# MCU.net
KiCad netlist of a schematic drawn in Altium Designer
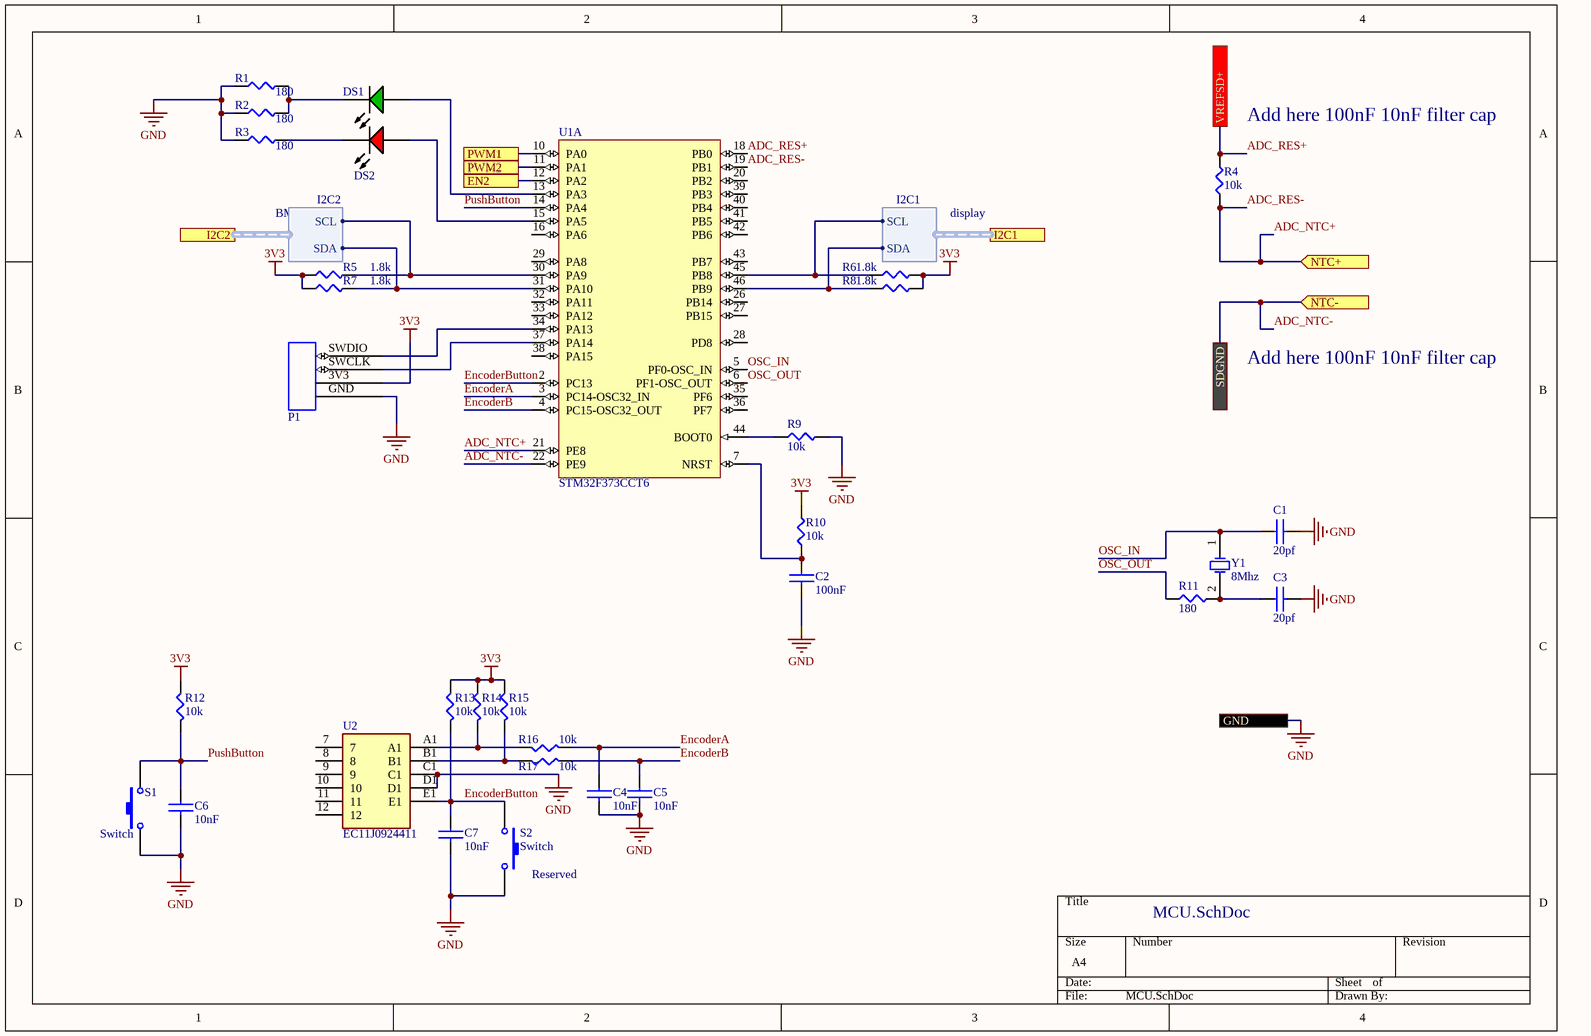
[diagram p0: MCU.SchDoc]

(export (version "E")
  (design (tool "Eeschema 10.0.6"))
  (components
    (comp (ref "C1")
      (value "20pf")
      (footprint "CAPC160X80X90L35N")
      (fields (field (name "LCSC PART #") "C1648") (field (name "PART NUMBER") "CL10C200JB8NNNC"))
      (libsource (lib "Miscellaneous") (part "capacitor"))
    )
    (comp (ref "C2")
      (value "100nF")
      (footprint "CAPC160X80X90L35N")
      (fields (field (name "LCSC PART #") "C14663") (field (name "PART NUMBER") "CC0603KRX7R9BB104"))
      (libsource (lib "Miscellaneous") (part "capacitor"))
    )
    (comp (ref "C3")
      (value "20pf")
      (footprint "CAPC160X80X90L35N")
      (fields (field (name "LCSC PART #") "C1648") (field (name "PART NUMBER") "CL10C200JB8NNNC"))
      (libsource (lib "Miscellaneous") (part "capacitor"))
    )
    (comp (ref "C4")
      (value "10nF")
      (footprint "CAPC160X80X90L35N")
      (fields (field (name "LCSC PART #") "C57112") (field (name "PART NUMBER") "0603B103K500NT"))
      (libsource (lib "Miscellaneous") (part "capacitor"))
    )
    (comp (ref "C5")
      (value "10nF")
      (footprint "CAPC160X80X90L35N")
      (fields (field (name "LCSC PART #") "C57112") (field (name "PART NUMBER") "0603B103K500NT"))
      (libsource (lib "Miscellaneous") (part "capacitor"))
    )
    (comp (ref "C6")
      (value "10nF")
      (footprint "CAPC160X80X90L35N")
      (fields (field (name "LCSC PART #") "C57112") (field (name "PART NUMBER") "0603B103K500NT"))
      (libsource (lib "Miscellaneous") (part "capacitor"))
    )
    (comp (ref "C7")
      (value "10nF")
      (footprint "CAPC160X80X90L35N")
      (fields (field (name "LCSC PART #") "C57112") (field (name "PART NUMBER") "0603B103K500NT"))
      (libsource (lib "Miscellaneous") (part "capacitor"))
    )
    (comp (ref "DS1")
      (value "19-217/GHC-YR1S2/3T")
      (footprint "LEDC160X80X60L30N")
      (description "Green LED")
      (fields (field (name "LCSC PART #") "C72043"))
      (libsource (lib "Miscellaneous") (part "LED"))
    )
    (comp (ref "DS2")
      (value "FC-2012HRK-620D")
      (footprint "LEDC200X125X110L30N")
      (description "Red LED")
      (fields (field (name "LCSC PART #") "C84256"))
      (libsource (lib "Miscellaneous") (part "RED LED"))
    )
    (comp (ref "P1") (value "SWD") (footprint "SWD") (libsource (lib "Miscellaneous") (part "SWD port")))
    (comp (ref "R1")
      (value "180")
      (footprint "RESC160X80X90L30N")
      (fields (field (name "PART NUMBER") "0603WAF1800T5E") (field (name "LCSC PART #") "C22828"))
      (libsource (lib "Miscellaneous") (part "Resistor"))
    )
    (comp (ref "R2")
      (value "180")
      (footprint "RESC160X80X90L30N")
      (fields (field (name "PART NUMBER") "0603WAF1800T5E") (field (name "LCSC PART #") "C22828"))
      (libsource (lib "Miscellaneous") (part "Resistor"))
    )
    (comp (ref "R3")
      (value "180")
      (footprint "RESC160X80X90L30N")
      (fields (field (name "PART NUMBER") "0603WAF1800T5E") (field (name "LCSC PART #") "C22828"))
      (libsource (lib "Miscellaneous") (part "Resistor"))
    )
    (comp (ref "R4")
      (value "10k")
      (footprint "RESC160X80X90L30N")
      (fields (field (name "PART NUMBER") "0603WAF1002T5E") (field (name "LCSC PART #") "C25804"))
      (libsource (lib "Miscellaneous") (part "Resistor"))
    )
    (comp (ref "R5")
      (value "1.8k")
      (footprint "RESC160X80X90L30N")
      (fields (field (name "PART NUMBER") "0603WAF1801T5E") (field (name "LCSC PART #") "C4177"))
      (libsource (lib "Miscellaneous") (part "Resistor"))
    )
    (comp (ref "R6")
      (value "1.8k")
      (footprint "RESC160X80X90L30N")
      (fields (field (name "PART NUMBER") "0603WAF1801T5E") (field (name "LCSC PART #") "C4177"))
      (libsource (lib "Miscellaneous") (part "Resistor"))
    )
    (comp (ref "R7")
      (value "1.8k")
      (footprint "RESC160X80X90L30N")
      (fields (field (name "PART NUMBER") "0603WAF1801T5E") (field (name "LCSC PART #") "C4177"))
      (libsource (lib "Miscellaneous") (part "Resistor"))
    )
    (comp (ref "R8")
      (value "1.8k")
      (footprint "RESC160X80X90L30N")
      (fields (field (name "PART NUMBER") "0603WAF1801T5E") (field (name "LCSC PART #") "C4177"))
      (libsource (lib "Miscellaneous") (part "Resistor"))
    )
    (comp (ref "R9")
      (value "10k")
      (footprint "RESC160X80X90L30N")
      (fields (field (name "PART NUMBER") "0603WAF1002T5E") (field (name "LCSC PART #") "C25804"))
      (libsource (lib "Miscellaneous") (part "Resistor"))
    )
    (comp (ref "R10")
      (value "10k")
      (footprint "RESC160X80X90L30N")
      (fields (field (name "PART NUMBER") "0603WAF1002T5E") (field (name "LCSC PART #") "C25804"))
      (libsource (lib "Miscellaneous") (part "Resistor"))
    )
    (comp (ref "R11")
      (value "180")
      (footprint "RESC160X80X90L30N")
      (fields (field (name "PART NUMBER") "0603WAF1800T5E") (field (name "LCSC PART #") "C22828"))
      (libsource (lib "Miscellaneous") (part "Resistor"))
    )
    (comp (ref "R12")
      (value "10k")
      (footprint "RESC160X80X90L30N")
      (fields (field (name "PART NUMBER") "0603WAF1002T5E") (field (name "LCSC PART #") "C25804"))
      (libsource (lib "Miscellaneous") (part "Resistor"))
    )
    (comp (ref "R13")
      (value "10k")
      (footprint "RESC160X80X90L30N")
      (fields (field (name "PART NUMBER") "0603WAF1002T5E") (field (name "LCSC PART #") "C25804"))
      (libsource (lib "Miscellaneous") (part "Resistor"))
    )
    (comp (ref "R14")
      (value "10k")
      (footprint "RESC160X80X90L30N")
      (fields (field (name "PART NUMBER") "0603WAF1002T5E") (field (name "LCSC PART #") "C25804"))
      (libsource (lib "Miscellaneous") (part "Resistor"))
    )
    (comp (ref "R15")
      (value "10k")
      (footprint "RESC160X80X90L30N")
      (fields (field (name "PART NUMBER") "0603WAF1002T5E") (field (name "LCSC PART #") "C25804"))
      (libsource (lib "Miscellaneous") (part "Resistor"))
    )
    (comp (ref "R16")
      (value "10k")
      (footprint "RESC160X80X90L30N")
      (fields (field (name "PART NUMBER") "0603WAF1002T5E") (field (name "LCSC PART #") "C25804"))
      (libsource (lib "Miscellaneous") (part "Resistor"))
    )
    (comp (ref "R17")
      (value "10k")
      (footprint "RESC160X80X90L30N")
      (fields (field (name "PART NUMBER") "0603WAF1002T5E") (field (name "LCSC PART #") "C25804"))
      (libsource (lib "Miscellaneous") (part "Resistor"))
    )
    (comp (ref "S1")
      (value "Switch")
      (footprint "Tactile switch")
      (fields (field (name "PART NUMBER") "TS-1187A-C-E-B") (field (name "PUBLISHER") "Altium Limited"))
      (libsource (lib "Miscellaneous") (part "Switch"))
    )
    (comp (ref "S2")
      (value "Switch")
      (footprint "Tactile switch")
      (fields (field (name "PART NUMBER") "TS-1187A-C-E-B") (field (name "PUBLISHER") "Altium Limited"))
      (libsource (lib "Miscellaneous") (part "Switch"))
    )
    (comp (ref "U1")
      (value "STM32F373CCT6")
      (footprint "STM-LQFP48_L")
      (fields (field (name "LCSC PART #") "C89403") (field (name "MANUFACTURER") "STMicroelectronics"))
      (libsource (lib "Miscellaneous") (part "STM32F373CCT6"))
    )
    (comp (ref "U2")
      (value "EC11J0924411")
      (footprint "EC11J0924411")
      (description "Rotary encoder")
      (fields (field (name "MOUSER2 PART NUMBER") "688-EC11J0924411"))
      (libsource (lib "Miscellaneous") (part "EC11J0924411"))
    )
    (comp (ref "Y1")
      (value "8Mhz")
      (footprint "5032")
      (description "Crystal Oscillator")
      (fields
        (field (name "PART NUMBER") "X50328MSB2GI")
        (field (name "LCSC PART #") "C115962")
        (field (name "PUBLISHER") "Altium Limited")
      )
      (libsource (lib "Miscellaneous") (part "XTAL"))
    )
  )
  (nets
    (net (code "3") (name "/ADC_NTC+") (class "Default")
      (node (ref "R4") (pin "1") (pinfunction "1_1") (pintype "passive"))
      (node (ref "U1") (pin "19") (pinfunction "PB1_19") (pintype "bidirectional"))
      (node (ref "U1") (pin "21") (pinfunction "PE8_21") (pintype "bidirectional"))
    )
    (net (code "4") (name "/ADC_NTC-") (class "Default")
      (node (ref "U1") (pin "22") (pinfunction "PE9_22") (pintype "bidirectional"))
    )
    (net (code "5") (name "/ADC_RES+") (class "Default")
      (node (ref "R4") (pin "2") (pinfunction "2_2") (pintype "passive"))
      (node (ref "U1") (pin "18") (pinfunction "PB0_18") (pintype "bidirectional"))
    )
    (net (code "6") (name "/EN2") (class "Default")
      (node (ref "U1") (pin "12") (pinfunction "PA2_12") (pintype "bidirectional"))
    )
    (net (code "7") (name "/EncoderA") (class "Default")
      (node (ref "C4") (pin "1") (pinfunction "1_1") (pintype "passive"))
      (node (ref "R16") (pin "2") (pinfunction "2_2") (pintype "passive"))
      (node (ref "U1") (pin "3") (pinfunction "PC14-OSC32_IN_3") (pintype "bidirectional"))
    )
    (net (code "8") (name "/EncoderB") (class "Default")
      (node (ref "C5") (pin "1") (pinfunction "1_1") (pintype "passive"))
      (node (ref "R17") (pin "2") (pinfunction "2_2") (pintype "passive"))
      (node (ref "U1") (pin "4") (pinfunction "PC15-OSC32_OUT_4") (pintype "bidirectional"))
    )
    (net (code "9") (name "/EncoderButton") (class "Default")
      (node (ref "C7") (pin "1") (pinfunction "1_1") (pintype "passive"))
      (node (ref "R13") (pin "2") (pinfunction "2_2") (pintype "passive"))
      (node (ref "S2") (pin "1") (pinfunction "1_1") (pintype "passive"))
      (node (ref "U1") (pin "2") (pinfunction "PC13_2") (pintype "bidirectional"))
      (node (ref "U2") (pin "E1") (pinfunction "E1_E1") (pintype "passive"))
    )
    (net (code "10") (name "/OSC_IN") (class "Default")
      (node (ref "C1") (pin "1") (pinfunction "1_1") (pintype "passive"))
      (node (ref "U1") (pin "5") (pinfunction "PF0-OSC_IN_5") (pintype "bidirectional"))
      (node (ref "Y1") (pin "1") (pinfunction "OSC1_1") (pintype "passive"))
    )
    (net (code "11") (name "/OSC_OUT") (class "Default")
      (node (ref "R11") (pin "1") (pinfunction "1_1") (pintype "passive"))
      (node (ref "U1") (pin "6") (pinfunction "PF1-OSC_OUT_6") (pintype "bidirectional"))
    )
    (net (code "12") (name "/PWM1") (class "Default")
      (node (ref "U1") (pin "10") (pinfunction "PA0_10") (pintype "bidirectional"))
    )
    (net (code "13") (name "/PWM2") (class "Default")
      (node (ref "U1") (pin "11") (pinfunction "PA1_11") (pintype "bidirectional"))
    )
    (net (code "14") (name "/PushButton") (class "Default")
      (node (ref "C6") (pin "1") (pinfunction "1_1") (pintype "passive"))
      (node (ref "R12") (pin "2") (pinfunction "2_2") (pintype "passive"))
      (node (ref "S1") (pin "2") (pinfunction "2_2") (pintype "passive"))
      (node (ref "U1") (pin "14") (pinfunction "PA4_14") (pintype "bidirectional"))
    )
    (net (code "17") (name "3V3") (class "Default")
      (node (ref "P1") (pin "3V3") (pinfunction "3V3_3V3") (pintype "power_in"))
      (node (ref "R10") (pin "2") (pinfunction "2_2") (pintype "passive"))
      (node (ref "R12") (pin "1") (pinfunction "1_1") (pintype "passive"))
      (node (ref "R13") (pin "1") (pinfunction "1_1") (pintype "passive"))
      (node (ref "R14") (pin "1") (pinfunction "1_1") (pintype "passive"))
      (node (ref "R15") (pin "1") (pinfunction "1_1") (pintype "passive"))
      (node (ref "R5") (pin "1") (pinfunction "1_1") (pintype "passive"))
      (node (ref "R6") (pin "2") (pinfunction "2_2") (pintype "passive"))
      (node (ref "R7") (pin "1") (pinfunction "1_1") (pintype "passive"))
      (node (ref "R8") (pin "2") (pinfunction "2_2") (pintype "passive"))
    )
    (net (code "18") (name "GND") (class "Default")
      (node (ref "C1") (pin "2") (pinfunction "2_2") (pintype "passive"))
      (node (ref "C2") (pin "2") (pinfunction "2_2") (pintype "passive"))
      (node (ref "C3") (pin "2") (pinfunction "2_2") (pintype "passive"))
      (node (ref "C4") (pin "2") (pinfunction "2_2") (pintype "passive"))
      (node (ref "C5") (pin "2") (pinfunction "2_2") (pintype "passive"))
      (node (ref "C6") (pin "2") (pinfunction "2_2") (pintype "passive"))
      (node (ref "C7") (pin "2") (pinfunction "2_2") (pintype "passive"))
      (node (ref "P1") (pin "GND") (pinfunction "GND_GND") (pintype "power_in"))
      (node (ref "R1") (pin "1") (pinfunction "1_1") (pintype "passive"))
      (node (ref "R2") (pin "1") (pinfunction "1_1") (pintype "passive"))
      (node (ref "R3") (pin "1") (pinfunction "1_1") (pintype "passive"))
      (node (ref "R9") (pin "2") (pinfunction "2_2") (pintype "passive"))
      (node (ref "S1") (pin "1") (pinfunction "1_1") (pintype "passive"))
      (node (ref "S2") (pin "2") (pinfunction "2_2") (pintype "passive"))
      (node (ref "U2") (pin "C1") (pinfunction "C1_C1") (pintype "passive"))
      (node (ref "U2") (pin "D1") (pinfunction "D1_D1") (pintype "passive"))
    )
    (net (code "19") (name "Net-(DS1-PadC)") (class "Default")
      (node (ref "DS1") (pin "C") (pinfunction "C_C") (pintype "passive"))
      (node (ref "R1") (pin "2") (pinfunction "2_2") (pintype "passive"))
      (node (ref "R2") (pin "2") (pinfunction "2_2") (pintype "passive"))
    )
    (net (code "20") (name "Net-(DS2-PadC)") (class "Default")
      (node (ref "DS2") (pin "C") (pinfunction "C_C") (pintype "passive"))
      (node (ref "R3") (pin "2") (pinfunction "2_2") (pintype "passive"))
    )
    (net (code "21") (name "Net-(R14-Pad2)") (class "Default")
      (node (ref "R14") (pin "2") (pinfunction "2_2") (pintype "passive"))
      (node (ref "R16") (pin "1") (pinfunction "1_1") (pintype "passive"))
      (node (ref "U2") (pin "A1") (pinfunction "A1_A1") (pintype "passive"))
    )
    (net (code "22") (name "Net-(R15-Pad2)") (class "Default")
      (node (ref "R15") (pin "2") (pinfunction "2_2") (pintype "passive"))
      (node (ref "R17") (pin "1") (pinfunction "1_1") (pintype "passive"))
      (node (ref "U2") (pin "B1") (pinfunction "B1_B1") (pintype "passive"))
    )
    (net (code "23") (name "Net-(U1A-BOOT0)") (class "Default")
      (node (ref "R9") (pin "1") (pinfunction "1_1") (pintype "passive"))
      (node (ref "U1") (pin "44") (pinfunction "BOOT0_44") (pintype "input"))
    )
    (net (code "24") (name "Net-(U1A-NRST)") (class "Default")
      (node (ref "C2") (pin "1") (pinfunction "1_1") (pintype "passive"))
      (node (ref "R10") (pin "1") (pinfunction "1_1") (pintype "passive"))
      (node (ref "U1") (pin "7") (pinfunction "NRST_7") (pintype "bidirectional"))
    )
    (net (code "25") (name "Net-(U1A-PA3)") (class "Default")
      (node (ref "DS1") (pin "A") (pinfunction "A_A") (pintype "passive"))
      (node (ref "U1") (pin "13") (pinfunction "PA3_13") (pintype "bidirectional"))
    )
    (net (code "26") (name "Net-(U1A-PA5)") (class "Default")
      (node (ref "DS2") (pin "A") (pinfunction "A_A") (pintype "passive"))
      (node (ref "U1") (pin "15") (pinfunction "PA5_15") (pintype "bidirectional"))
    )
    (net (code "27") (name "Net-(U1A-PA9)") (class "Default")
      (node (ref "R5") (pin "2") (pinfunction "2_2") (pintype "passive"))
      (node (ref "U1") (pin "30") (pinfunction "PA9_30") (pintype "bidirectional"))
    )
    (net (code "28") (name "Net-(U1A-PA10)") (class "Default")
      (node (ref "R7") (pin "2") (pinfunction "2_2") (pintype "passive"))
      (node (ref "U1") (pin "31") (pinfunction "PA10_31") (pintype "bidirectional"))
    )
    (net (code "29") (name "Net-(U1A-PA13)") (class "Default")
      (node (ref "P1") (pin "SWDIO") (pinfunction "SWDIO_SWDIO") (pintype "bidirectional"))
      (node (ref "U1") (pin "34") (pinfunction "PA13_34") (pintype "bidirectional"))
    )
    (net (code "30") (name "Net-(U1A-PA14)") (class "Default")
      (node (ref "P1") (pin "SWCLK") (pinfunction "SWCLK_SWCLK") (pintype "bidirectional"))
      (node (ref "U1") (pin "37") (pinfunction "PA14_37") (pintype "bidirectional"))
    )
    (net (code "31") (name "Net-(U1A-PB8)") (class "Default")
      (node (ref "R6") (pin "1") (pinfunction "1_1") (pintype "passive"))
      (node (ref "U1") (pin "45") (pinfunction "PB8_45") (pintype "bidirectional"))
    )
    (net (code "32") (name "Net-(U1A-PB9)") (class "Default")
      (node (ref "R8") (pin "1") (pinfunction "1_1") (pintype "passive"))
      (node (ref "U1") (pin "46") (pinfunction "PB9_46") (pintype "bidirectional"))
    )
    (net (code "33") (name "Net-(Y1-OSC2)") (class "Default")
      (node (ref "C3") (pin "1") (pinfunction "1_1") (pintype "passive"))
      (node (ref "R11") (pin "2") (pinfunction "2_2") (pintype "passive"))
      (node (ref "Y1") (pin "2") (pinfunction "OSC2_2") (pintype "passive"))
    )
    (net (code "34") (name "unconnected-(U1A-PA6-Pad16)") (class "Default")
      (node (ref "U1") (pin "16") (pinfunction "PA6_16") (pintype "bidirectional"))
    )
    (net (code "35") (name "unconnected-(U1A-PA8-Pad29)") (class "Default")
      (node (ref "U1") (pin "29") (pinfunction "PA8_29") (pintype "bidirectional"))
    )
    (net (code "36") (name "unconnected-(U1A-PA11-Pad32)") (class "Default")
      (node (ref "U1") (pin "32") (pinfunction "PA11_32") (pintype "bidirectional"))
    )
    (net (code "37") (name "unconnected-(U1A-PA12-Pad33)") (class "Default")
      (node (ref "U1") (pin "33") (pinfunction "PA12_33") (pintype "bidirectional"))
    )
    (net (code "38") (name "unconnected-(U1A-PA15-Pad38)") (class "Default")
      (node (ref "U1") (pin "38") (pinfunction "PA15_38") (pintype "bidirectional"))
    )
    (net (code "39") (name "unconnected-(U1A-PB2-Pad20)") (class "Default")
      (node (ref "U1") (pin "20") (pinfunction "PB2_20") (pintype "bidirectional"))
    )
    (net (code "40") (name "unconnected-(U1A-PB3-Pad39)") (class "Default")
      (node (ref "U1") (pin "39") (pinfunction "PB3_39") (pintype "bidirectional"))
    )
    (net (code "41") (name "unconnected-(U1A-PB4-Pad40)") (class "Default")
      (node (ref "U1") (pin "40") (pinfunction "PB4_40") (pintype "bidirectional"))
    )
    (net (code "42") (name "unconnected-(U1A-PB5-Pad41)") (class "Default")
      (node (ref "U1") (pin "41") (pinfunction "PB5_41") (pintype "bidirectional"))
    )
    (net (code "43") (name "unconnected-(U1A-PB6-Pad42)") (class "Default")
      (node (ref "U1") (pin "42") (pinfunction "PB6_42") (pintype "bidirectional"))
    )
    (net (code "44") (name "unconnected-(U1A-PB7-Pad43)") (class "Default")
      (node (ref "U1") (pin "43") (pinfunction "PB7_43") (pintype "bidirectional"))
    )
    (net (code "45") (name "unconnected-(U1A-PB14-Pad26)") (class "Default")
      (node (ref "U1") (pin "26") (pinfunction "PB14_26") (pintype "bidirectional"))
    )
    (net (code "46") (name "unconnected-(U1A-PB15-Pad27)") (class "Default")
      (node (ref "U1") (pin "27") (pinfunction "PB15_27") (pintype "bidirectional"))
    )
    (net (code "47") (name "unconnected-(U1A-PD8-Pad28)") (class "Default")
      (node (ref "U1") (pin "28") (pinfunction "PD8_28") (pintype "bidirectional"))
    )
    (net (code "48") (name "unconnected-(U1A-PF6-Pad35)") (class "Default")
      (node (ref "U1") (pin "35") (pinfunction "PF6_35") (pintype "bidirectional"))
    )
    (net (code "49") (name "unconnected-(U1A-PF7-Pad36)") (class "Default")
      (node (ref "U1") (pin "36") (pinfunction "PF7_36") (pintype "bidirectional"))
    )
    (net (code "50") (name "unconnected-(U2-Pad7)") (class "Default")
      (node (ref "U2") (pin "7") (pinfunction "7_7") (pintype "passive"))
    )
    (net (code "51") (name "unconnected-(U2-Pad8)") (class "Default")
      (node (ref "U2") (pin "8") (pinfunction "8_8") (pintype "passive"))
    )
    (net (code "52") (name "unconnected-(U2-Pad9)") (class "Default")
      (node (ref "U2") (pin "9") (pinfunction "9_9") (pintype "passive"))
    )
    (net (code "53") (name "unconnected-(U2-Pad10)") (class "Default")
      (node (ref "U2") (pin "10") (pinfunction "10_10") (pintype "passive"))
    )
    (net (code "54") (name "unconnected-(U2-Pad11)") (class "Default")
      (node (ref "U2") (pin "11") (pinfunction "11_11") (pintype "passive"))
    )
    (net (code "55") (name "unconnected-(U2-Pad12)") (class "Default")
      (node (ref "U2") (pin "12") (pinfunction "12_12") (pintype "passive"))
    )
  )
)
